# POWER.net
KiCad netlist of a schematic drawn in Altium Designer
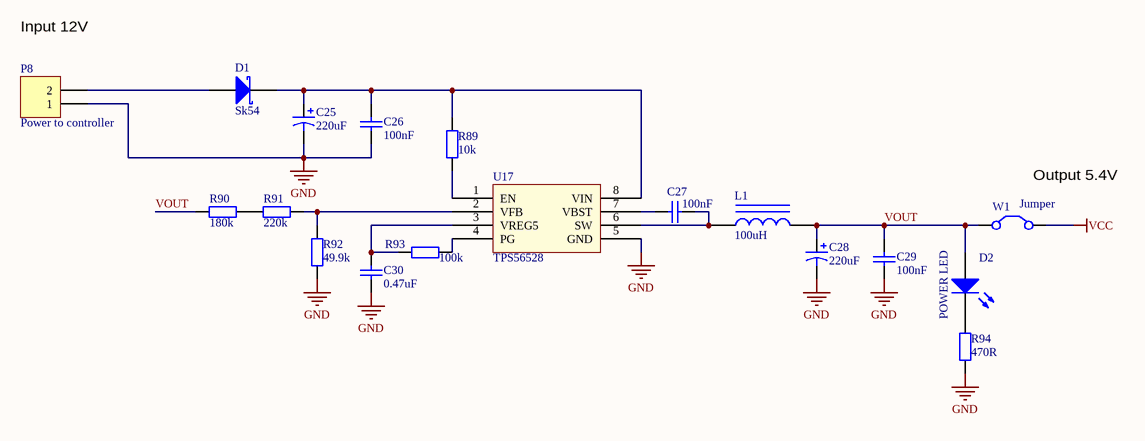
[diagram p0: POWER.SchDoc]

(export (version "E")
  (design (tool "Eeschema 10.0.6"))
  (components
    (comp (ref "C25")
      (value "220uF")
      (footprint "SMD CAPACITOR 220uF")
      (description "Capacitor")
      (fields (field (name "PUBLISHER") "Altium Limited"))
      (libsource (lib "Miscellaneous Devices") (part "Cap Pol1"))
    )
    (comp (ref "C26")
      (value "100nF")
      (footprint "1608[0603]")
      (description "Capacitor")
      (fields (field (name "PUBLISHER") "Altium Limited"))
      (libsource (lib "Miscellaneous Devices") (part "Cap"))
    )
    (comp (ref "C27")
      (value "100nF")
      (footprint "1608[0603]")
      (description "Capacitor")
      (fields (field (name "PUBLISHER") "Altium Limited"))
      (libsource (lib "Miscellaneous Devices") (part "Cap"))
    )
    (comp (ref "C28")
      (value "220uF")
      (footprint "SMD CAPACITOR 220uF")
      (description "Capacitor")
      (fields (field (name "PUBLISHER") "Altium Limited"))
      (libsource (lib "Miscellaneous Devices") (part "Cap Pol1"))
    )
    (comp (ref "C29")
      (value "100nF")
      (footprint "1608[0603]")
      (description "Capacitor")
      (fields (field (name "PUBLISHER") "Altium Limited"))
      (libsource (lib "Miscellaneous Devices") (part "Cap"))
    )
    (comp (ref "C30")
      (value "0.47uF")
      (footprint "1608[0603]")
      (description "Capacitor")
      (fields (field (name "PUBLISHER") "Altium Limited"))
      (libsource (lib "Miscellaneous Devices") (part "Cap"))
    )
    (comp (ref "D1")
      (value "Sk54")
      (footprint "DIODE SMC 6x7mm")
      (description "Schottky Diode")
      (fields (field (name "PUBLISHER") "Altium Limited"))
      (libsource (lib "Miscellaneous Devices") (part "D Schottky"))
    )
    (comp (ref "D2")
      (value "POWER LED")
      (footprint "LED-1")
      (description "Typical INFRARED GaAs LED")
      (fields (field (name "PUBLISHER") "Altium Limited"))
      (libsource (lib "Miscellaneous Devices") (part "LED0"))
    )
    (comp (ref "L1")
      (value "100uH")
      (footprint "SMD Inductor 12x12mm")
      (description "Magnetic-Core Inductor")
      (fields (field (name "PUBLISHER") "Altium Limited"))
      (libsource (lib "Miscellaneous Devices") (part "Inductor Iron"))
    )
    (comp (ref "P8")
      (value "Power to controller")
      (footprint "Block2 - 3.81")
      (description "Header, 2-Pin")
      (fields (field (name "PUBLISHER") "Altium Limited"))
      (libsource (lib "Miscellaneous Connectors") (part "Header 2"))
    )
    (comp (ref "R89")
      (value "10k")
      (footprint "1608[0603]")
      (description "Resistor")
      (fields (field (name "PUBLISHER") "Altium Limited"))
      (libsource (lib "") (part "Res2_1"))
    )
    (comp (ref "R90")
      (value "180k")
      (footprint "6-0805_L")
      (description "Resistor")
      (fields (field (name "PUBLISHER") "Altium Limited"))
      (libsource (lib "Miscellaneous Devices") (part "Res2"))
    )
    (comp (ref "R91")
      (value "220k")
      (footprint "6-0805_L")
      (description "Resistor")
      (fields (field (name "PUBLISHER") "Altium Limited"))
      (libsource (lib "Miscellaneous Devices") (part "Res2"))
    )
    (comp (ref "R92")
      (value "49.9k")
      (footprint "1608[0603]")
      (description "Resistor")
      (fields (field (name "PUBLISHER") "Altium Limited"))
      (libsource (lib "") (part "Res2_1"))
    )
    (comp (ref "R93")
      (value "100k")
      (footprint "1608[0603]")
      (description "Resistor")
      (fields (field (name "PUBLISHER") "Altium Limited"))
      (libsource (lib "Miscellaneous Devices") (part "Res2"))
    )
    (comp (ref "R94")
      (value "470R")
      (footprint "1608[0603]")
      (description "Resistor")
      (fields (field (name "PUBLISHER") "Altium Limited"))
      (libsource (lib "") (part "Res2_1"))
    )
    (comp (ref "U17")
      (value "TPS56528")
      (footprint "TPS56528")
      (description "Step-Down Converter 5A 4.5V-18V")
      (libsource (lib "LP_Lib") (part "TPS56528"))
    )
    (comp (ref "W1")
      (value "Jumper")
      (footprint "HDR1X2")
      (description "Jumper Wire")
      (fields (field (name "PUBLISHER") "Altium Limited"))
      (libsource (lib "Miscellaneous Devices") (part "Jumper"))
    )
  )
  (nets
    (net (code "1") (name "/VOUT") (class "Default")
      (node (ref "C28") (pin "1") (pinfunction "1_1") (pintype "passive"))
      (node (ref "C29") (pin "1") (pinfunction "1_1") (pintype "passive"))
      (node (ref "D2") (pin "1") (pinfunction "A_1") (pintype "passive"))
      (node (ref "L1") (pin "2") (pinfunction "2_2") (pintype "passive"))
      (node (ref "R90") (pin "2") (pinfunction "2_2") (pintype "passive"))
      (node (ref "W1") (pin "1") (pinfunction "C1_1") (pintype "passive"))
    )
    (net (code "2") (name "GND") (class "Default")
      (node (ref "C25") (pin "2") (pinfunction "2_2") (pintype "passive"))
      (node (ref "C26") (pin "2") (pinfunction "2_2") (pintype "passive"))
      (node (ref "C28") (pin "2") (pinfunction "2_2") (pintype "passive"))
      (node (ref "C29") (pin "2") (pinfunction "2_2") (pintype "passive"))
      (node (ref "C30") (pin "2") (pinfunction "2_2") (pintype "passive"))
      (node (ref "P8") (pin "1") (pinfunction "1_1") (pintype "passive"))
      (node (ref "R92") (pin "1") (pinfunction "1_1") (pintype "passive"))
      (node (ref "R94") (pin "1") (pinfunction "1_1") (pintype "passive"))
      (node (ref "U17") (pin "5") (pinfunction "GND_5") (pintype "passive"))
    )
    (net (code "3") (name "Net-(D1-A)") (class "Default")
      (node (ref "D1") (pin "1") (pinfunction "A_1") (pintype "passive"))
      (node (ref "P8") (pin "2") (pinfunction "2_2") (pintype "passive"))
    )
    (net (code "4") (name "Net-(D1-K)") (class "Default")
      (node (ref "C25") (pin "1") (pinfunction "1_1") (pintype "passive"))
      (node (ref "C26") (pin "1") (pinfunction "1_1") (pintype "passive"))
      (node (ref "D1") (pin "2") (pinfunction "K_2") (pintype "passive"))
      (node (ref "R89") (pin "2") (pinfunction "2_2") (pintype "passive"))
      (node (ref "U17") (pin "8") (pinfunction "VIN_8") (pintype "passive"))
    )
    (net (code "5") (name "Net-(D2-K)") (class "Default")
      (node (ref "D2") (pin "2") (pinfunction "K_2") (pintype "passive"))
      (node (ref "R94") (pin "2") (pinfunction "2_2") (pintype "passive"))
    )
    (net (code "6") (name "Net-(R90-Pad1)") (class "Default")
      (node (ref "R90") (pin "1") (pinfunction "1_1") (pintype "passive"))
      (node (ref "R91") (pin "2") (pinfunction "2_2") (pintype "passive"))
    )
    (net (code "7") (name "Net-(U17-EN)") (class "Default")
      (node (ref "R89") (pin "1") (pinfunction "1_1") (pintype "passive"))
      (node (ref "U17") (pin "1") (pinfunction "EN_1") (pintype "passive"))
    )
    (net (code "8") (name "Net-(U17-PG)") (class "Default")
      (node (ref "R93") (pin "1") (pinfunction "1_1") (pintype "passive"))
      (node (ref "U17") (pin "4") (pinfunction "PG_4") (pintype "passive"))
    )
    (net (code "9") (name "Net-(U17-SW)") (class "Default")
      (node (ref "C27") (pin "2") (pinfunction "2_2") (pintype "passive"))
      (node (ref "L1") (pin "1") (pinfunction "1_1") (pintype "passive"))
      (node (ref "U17") (pin "6") (pinfunction "SW_6") (pintype "passive"))
    )
    (net (code "10") (name "Net-(U17-VBST)") (class "Default")
      (node (ref "C27") (pin "1") (pinfunction "1_1") (pintype "passive"))
      (node (ref "U17") (pin "7") (pinfunction "VBST_7") (pintype "passive"))
    )
    (net (code "11") (name "Net-(U17-VFB)") (class "Default")
      (node (ref "R91") (pin "1") (pinfunction "1_1") (pintype "passive"))
      (node (ref "R92") (pin "2") (pinfunction "2_2") (pintype "passive"))
      (node (ref "U17") (pin "2") (pinfunction "VFB_2") (pintype "passive"))
    )
    (net (code "12") (name "Net-(U17-VREG5)") (class "Default")
      (node (ref "C30") (pin "1") (pinfunction "1_1") (pintype "passive"))
      (node (ref "R93") (pin "2") (pinfunction "2_2") (pintype "passive"))
      (node (ref "U17") (pin "3") (pinfunction "VREG5_3") (pintype "passive"))
    )
    (net (code "13") (name "VCC") (class "Default")
      (node (ref "W1") (pin "2") (pinfunction "C2_2") (pintype "passive"))
    )
  )
)
